# swarm.net
KiCad netlist of a schematic drawn in EAGLE
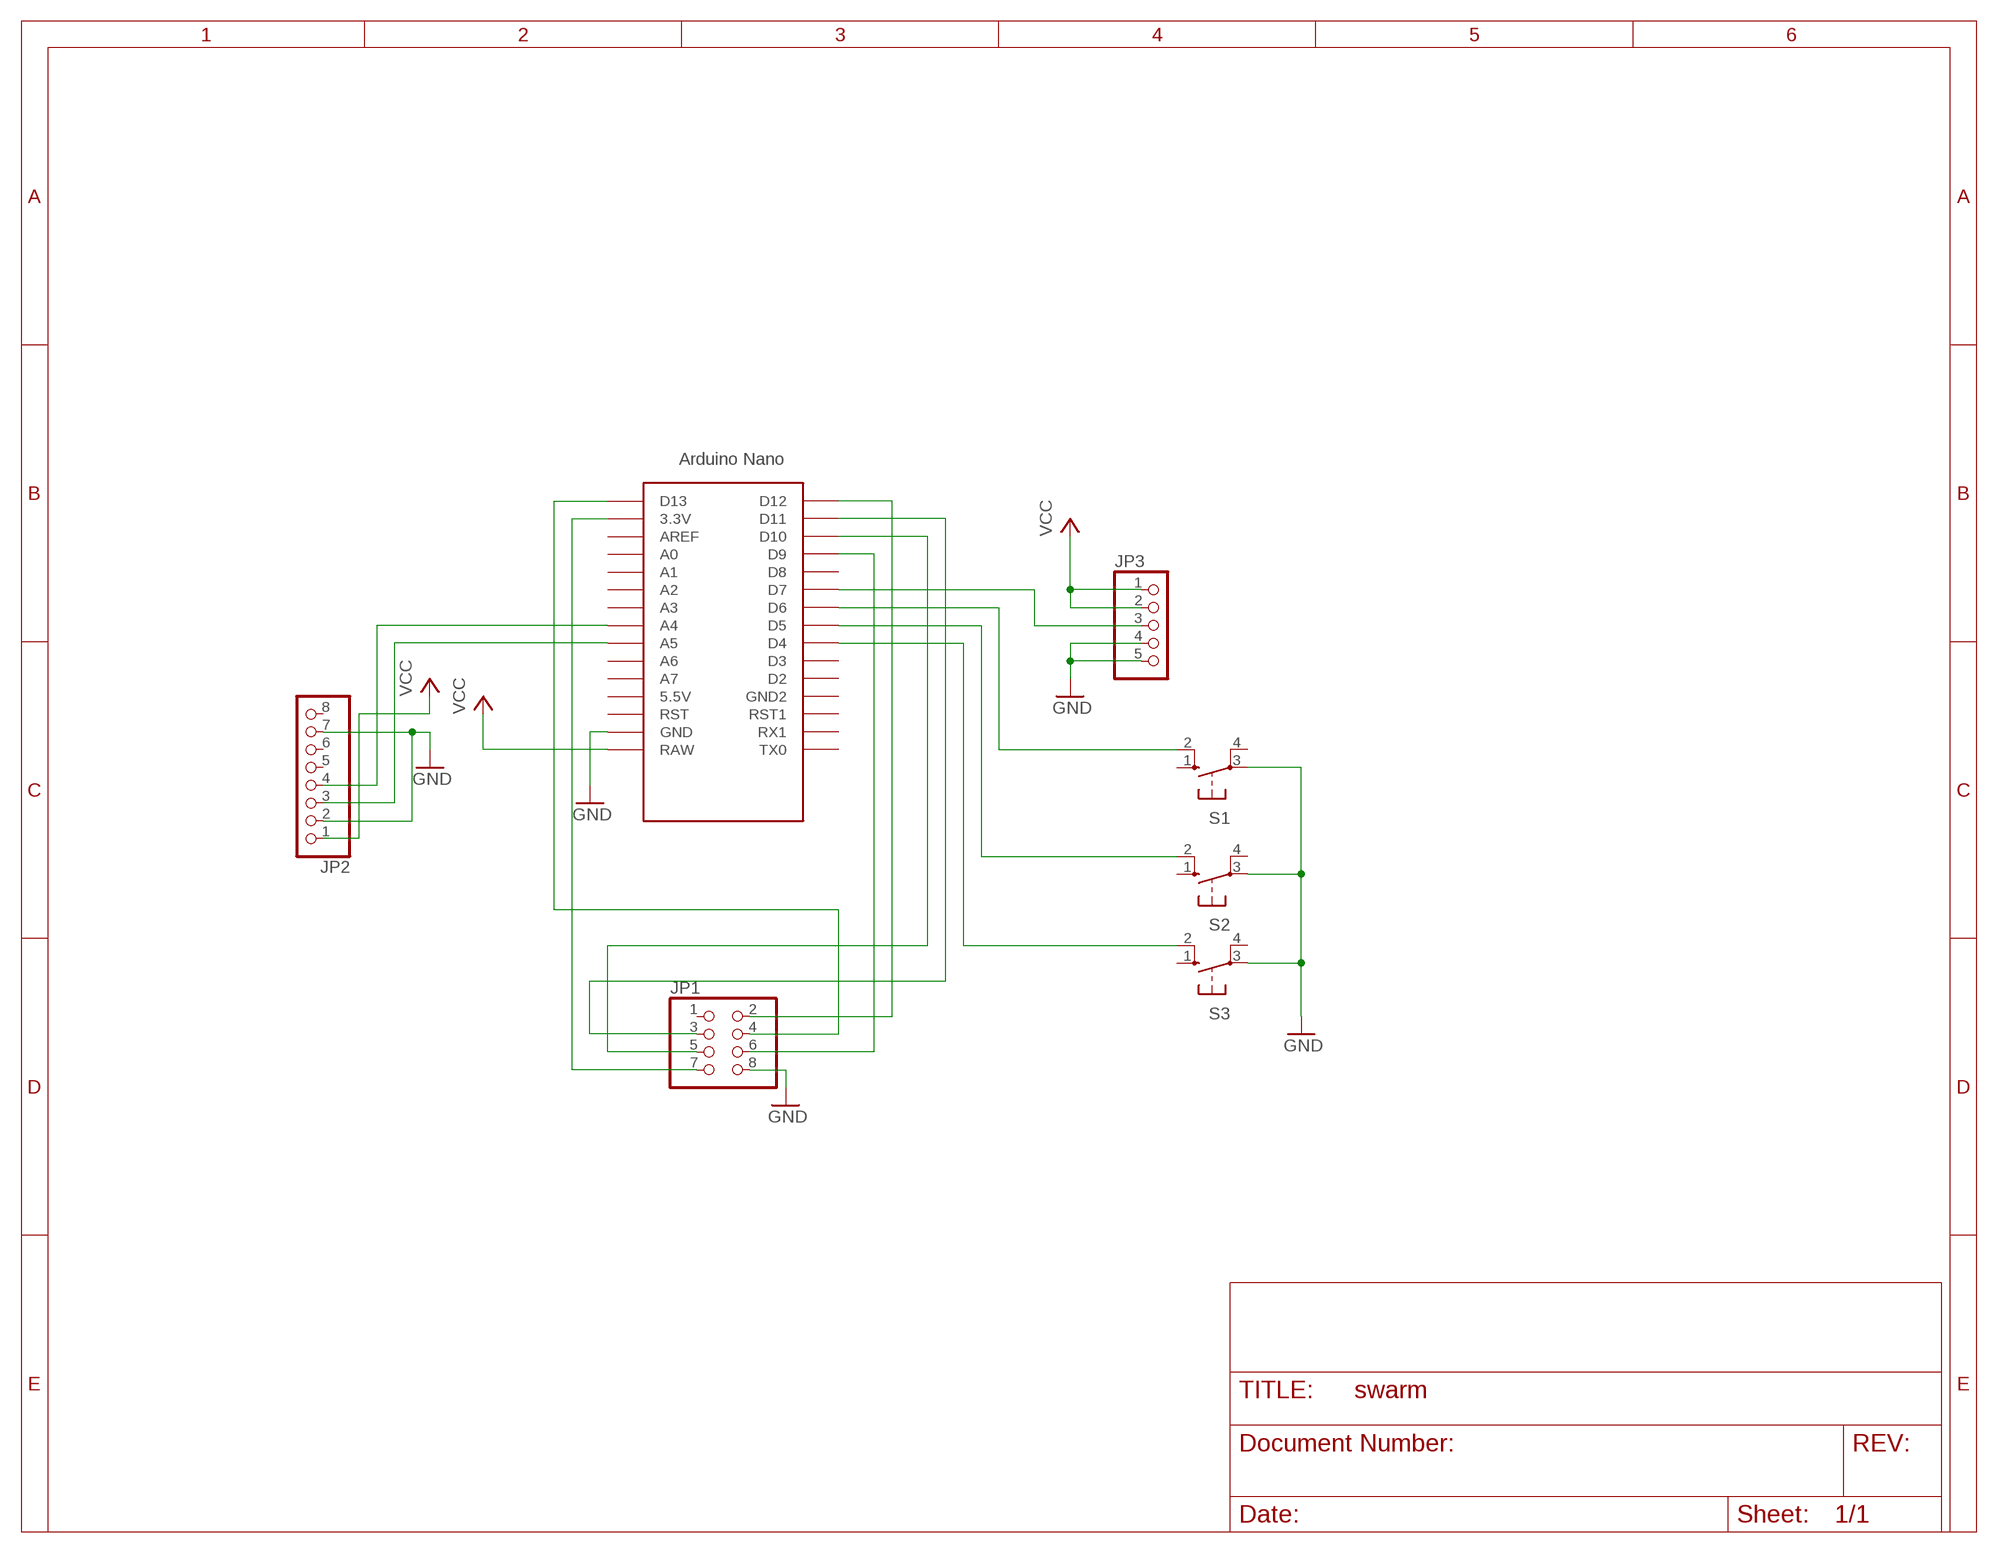
[diagram p0: schematic, sheet 1]

(export (version "E")
  (design (tool "Eeschema 10.0.6"))
  (components
    (comp (ref "JP1")
      (value "PINHD-2X4")
      (footprint "eagle-import:2X04")
      (libsource (lib "eagle-import") (part "PINHD-2X4"))
    )
    (comp (ref "JP2")
      (value "PINHD-1X8")
      (footprint "eagle-import:1X08")
      (libsource (lib "eagle-import") (part "PINHD-1X8"))
    )
    (comp (ref "JP3")
      (value "PINHD-1X5")
      (footprint "eagle-import:1X05")
      (libsource (lib "eagle-import") (part "PINHD-1X5"))
    )
    (comp (ref "S1")
      (value "10-XX")
      (footprint "eagle-import:B3F-10XX")
      (fields (field (name "MPN") "B3F-1000"))
      (libsource (lib "eagle-import") (part "10-XX"))
    )
    (comp (ref "S2")
      (value "10-XX")
      (footprint "eagle-import:B3F-10XX")
      (fields (field (name "MPN") "B3F-1000"))
      (libsource (lib "eagle-import") (part "10-XX"))
    )
    (comp (ref "S3")
      (value "10-XX")
      (footprint "eagle-import:B3F-10XX")
      (fields (field (name "MPN") "B3F-1000"))
      (libsource (lib "eagle-import") (part "10-XX"))
    )
    (comp (ref "U$1")
      (value "NANO")
      (footprint "eagle-import:NANO")
      (libsource (lib "eagle-import") (part "NANO"))
    )
  )
  (nets
    (net (code "1") (name "GND") (class "Default")
      (node (ref "JP1") (pin "8") (pinfunction "8_8") (pintype "passive"))
      (node (ref "JP2") (pin "2") (pinfunction "2_2") (pintype "passive"))
      (node (ref "JP2") (pin "7") (pinfunction "7_7") (pintype "passive"))
      (node (ref "JP3") (pin "4") (pinfunction "4_4") (pintype "passive"))
      (node (ref "JP3") (pin "5") (pinfunction "5_5") (pintype "passive"))
      (node (ref "S1") (pin "3") (pinfunction "P_3") (pintype "passive"))
      (node (ref "S2") (pin "3") (pinfunction "P_3") (pintype "passive"))
      (node (ref "S3") (pin "3") (pinfunction "P_3") (pintype "passive"))
      (node (ref "U$1") (pin "GND") (pinfunction "GND_GND") (pintype "bidirectional"))
    )
    (net (code "2") (name "Net-(JP1-Pad2)") (class "Default")
      (node (ref "JP1") (pin "2") (pinfunction "2_2") (pintype "passive"))
      (node (ref "U$1") (pin "D12") (pinfunction "D12_D12") (pintype "bidirectional"))
    )
    (net (code "3") (name "Net-(JP1-Pad3)") (class "Default")
      (node (ref "JP1") (pin "3") (pinfunction "3_3") (pintype "passive"))
      (node (ref "U$1") (pin "D11") (pinfunction "D11_D11") (pintype "bidirectional"))
    )
    (net (code "4") (name "Net-(JP1-Pad4)") (class "Default")
      (node (ref "JP1") (pin "4") (pinfunction "4_4") (pintype "passive"))
      (node (ref "U$1") (pin "D13") (pinfunction "D13_D13") (pintype "bidirectional"))
    )
    (net (code "5") (name "Net-(JP1-Pad5)") (class "Default")
      (node (ref "JP1") (pin "5") (pinfunction "5_5") (pintype "passive"))
      (node (ref "U$1") (pin "D10") (pinfunction "D10_D10") (pintype "bidirectional"))
    )
    (net (code "6") (name "Net-(JP1-Pad6)") (class "Default")
      (node (ref "JP1") (pin "6") (pinfunction "6_6") (pintype "passive"))
      (node (ref "U$1") (pin "D9") (pinfunction "D9_D9") (pintype "bidirectional"))
    )
    (net (code "7") (name "Net-(JP1-Pad7)") (class "Default")
      (node (ref "JP1") (pin "7") (pinfunction "7_7") (pintype "passive"))
      (node (ref "U$1") (pin "3.3V") (pinfunction "3.3V_3.3V") (pintype "bidirectional"))
    )
    (net (code "8") (name "Net-(JP2-Pad3)") (class "Default")
      (node (ref "JP2") (pin "3") (pinfunction "3_3") (pintype "passive"))
      (node (ref "U$1") (pin "A5") (pinfunction "A5_A5") (pintype "bidirectional"))
    )
    (net (code "9") (name "Net-(JP2-Pad4)") (class "Default")
      (node (ref "JP2") (pin "4") (pinfunction "4_4") (pintype "passive"))
      (node (ref "U$1") (pin "A4") (pinfunction "A4_A4") (pintype "bidirectional"))
    )
    (net (code "10") (name "Net-(JP3-Pad3)") (class "Default")
      (node (ref "JP3") (pin "3") (pinfunction "3_3") (pintype "passive"))
      (node (ref "U$1") (pin "D7") (pinfunction "D7_D7") (pintype "bidirectional"))
    )
    (net (code "11") (name "Net-(S1-S1)") (class "Default")
      (node (ref "S1") (pin "2") (pinfunction "S1_2") (pintype "passive"))
      (node (ref "U$1") (pin "D6") (pinfunction "D6_D6") (pintype "bidirectional"))
    )
    (net (code "12") (name "Net-(S2-S1)") (class "Default")
      (node (ref "S2") (pin "2") (pinfunction "S1_2") (pintype "passive"))
      (node (ref "U$1") (pin "D5") (pinfunction "D5_D5") (pintype "bidirectional"))
    )
    (net (code "13") (name "Net-(S3-S1)") (class "Default")
      (node (ref "S3") (pin "2") (pinfunction "S1_2") (pintype "passive"))
      (node (ref "U$1") (pin "D4") (pinfunction "D4_D4") (pintype "bidirectional"))
    )
    (net (code "14") (name "VCC") (class "Default")
      (node (ref "JP2") (pin "1") (pinfunction "1_1") (pintype "passive"))
      (node (ref "JP3") (pin "1") (pinfunction "1_1") (pintype "passive"))
      (node (ref "JP3") (pin "2") (pinfunction "2_2") (pintype "passive"))
      (node (ref "U$1") (pin "RAW") (pinfunction "RAW_RAW") (pintype "bidirectional"))
    )
    (net (code "15") (name "unconnected-(JP1-Pad1)") (class "Default")
      (node (ref "JP1") (pin "1") (pinfunction "1_1") (pintype "passive"))
    )
    (net (code "16") (name "unconnected-(JP2-Pad5)") (class "Default")
      (node (ref "JP2") (pin "5") (pinfunction "5_5") (pintype "passive"))
    )
    (net (code "17") (name "unconnected-(JP2-Pad6)") (class "Default")
      (node (ref "JP2") (pin "6") (pinfunction "6_6") (pintype "passive"))
    )
    (net (code "18") (name "unconnected-(JP2-Pad8)") (class "Default")
      (node (ref "JP2") (pin "8") (pinfunction "8_8") (pintype "passive"))
    )
    (net (code "19") (name "unconnected-(S1-P1-Pad4)") (class "Default")
      (node (ref "S1") (pin "4") (pinfunction "P1_4") (pintype "passive"))
    )
    (net (code "20") (name "unconnected-(S1-S-Pad1)") (class "Default")
      (node (ref "S1") (pin "1") (pinfunction "S_1") (pintype "passive"))
    )
    (net (code "21") (name "unconnected-(S2-P1-Pad4)") (class "Default")
      (node (ref "S2") (pin "4") (pinfunction "P1_4") (pintype "passive"))
    )
    (net (code "22") (name "unconnected-(S2-S-Pad1)") (class "Default")
      (node (ref "S2") (pin "1") (pinfunction "S_1") (pintype "passive"))
    )
    (net (code "23") (name "unconnected-(S3-P1-Pad4)") (class "Default")
      (node (ref "S3") (pin "4") (pinfunction "P1_4") (pintype "passive"))
    )
    (net (code "24") (name "unconnected-(S3-S-Pad1)") (class "Default")
      (node (ref "S3") (pin "1") (pinfunction "S_1") (pintype "passive"))
    )
    (net (code "25") (name "unconnected-(U$1-5.5V-Pad5V)") (class "Default")
      (node (ref "U$1") (pin "5V") (pinfunction "5.5V_5V") (pintype "bidirectional"))
    )
    (net (code "26") (name "unconnected-(U$1-GND2-PadGND1)") (class "Default")
      (node (ref "U$1") (pin "GND1") (pinfunction "GND2_GND1") (pintype "bidirectional"))
    )
    (net (code "27") (name "unconnected-(U$1-PadA0)") (class "Default")
      (node (ref "U$1") (pin "A0") (pinfunction "A0_A0") (pintype "bidirectional"))
    )
    (net (code "28") (name "unconnected-(U$1-PadA1)") (class "Default")
      (node (ref "U$1") (pin "A1") (pinfunction "A1_A1") (pintype "bidirectional"))
    )
    (net (code "29") (name "unconnected-(U$1-PadA2)") (class "Default")
      (node (ref "U$1") (pin "A2") (pinfunction "A2_A2") (pintype "bidirectional"))
    )
    (net (code "30") (name "unconnected-(U$1-PadA3)") (class "Default")
      (node (ref "U$1") (pin "A3") (pinfunction "A3_A3") (pintype "bidirectional"))
    )
    (net (code "31") (name "unconnected-(U$1-PadA6)") (class "Default")
      (node (ref "U$1") (pin "A6") (pinfunction "A6_A6") (pintype "bidirectional"))
    )
    (net (code "32") (name "unconnected-(U$1-PadA7)") (class "Default")
      (node (ref "U$1") (pin "A7") (pinfunction "A7_A7") (pintype "bidirectional"))
    )
    (net (code "33") (name "unconnected-(U$1-PadAREF)") (class "Default")
      (node (ref "U$1") (pin "AREF") (pinfunction "AREF_AREF") (pintype "bidirectional"))
    )
    (net (code "34") (name "unconnected-(U$1-PadD2)") (class "Default")
      (node (ref "U$1") (pin "D2") (pinfunction "D2_D2") (pintype "bidirectional"))
    )
    (net (code "35") (name "unconnected-(U$1-PadD3)") (class "Default")
      (node (ref "U$1") (pin "D3") (pinfunction "D3_D3") (pintype "bidirectional"))
    )
    (net (code "36") (name "unconnected-(U$1-PadD8)") (class "Default")
      (node (ref "U$1") (pin "D8") (pinfunction "D8_D8") (pintype "bidirectional"))
    )
    (net (code "37") (name "unconnected-(U$1-PadICSP1)") (class "Default")
      (node (ref "U$1") (pin "ICSP1") (pinfunction "ICSP1_ICSP1") (pintype "bidirectional"))
    )
    (net (code "38") (name "unconnected-(U$1-PadICSP2)") (class "Default")
      (node (ref "U$1") (pin "ICSP2") (pinfunction "ICSP2_ICSP2") (pintype "bidirectional"))
    )
    (net (code "39") (name "unconnected-(U$1-PadICSP3)") (class "Default")
      (node (ref "U$1") (pin "ICSP3") (pinfunction "ICSP3_ICSP3") (pintype "bidirectional"))
    )
    (net (code "40") (name "unconnected-(U$1-PadICSP4)") (class "Default")
      (node (ref "U$1") (pin "ICSP4") (pinfunction "ICSP4_ICSP4") (pintype "bidirectional"))
    )
    (net (code "41") (name "unconnected-(U$1-PadICSP5)") (class "Default")
      (node (ref "U$1") (pin "ICSP5") (pinfunction "ICSP5_ICSP5") (pintype "bidirectional"))
    )
    (net (code "42") (name "unconnected-(U$1-PadICSP6)") (class "Default")
      (node (ref "U$1") (pin "ICSP6") (pinfunction "ICSP6_ICSP6") (pintype "bidirectional"))
    )
    (net (code "43") (name "unconnected-(U$1-PadRST)") (class "Default")
      (node (ref "U$1") (pin "RST") (pinfunction "RST_RST") (pintype "bidirectional"))
    )
    (net (code "44") (name "unconnected-(U$1-PadRST1)") (class "Default")
      (node (ref "U$1") (pin "RST1") (pinfunction "RST1_RST1") (pintype "bidirectional"))
    )
    (net (code "45") (name "unconnected-(U$1-PadRX1)") (class "Default")
      (node (ref "U$1") (pin "RX1") (pinfunction "RX1_RX1") (pintype "bidirectional"))
    )
    (net (code "46") (name "unconnected-(U$1-PadTX0)") (class "Default")
      (node (ref "U$1") (pin "TX0") (pinfunction "TX0_TX0") (pintype "bidirectional"))
    )
  )
)
